# board_smart_switch.net
KiCad netlist of a schematic drawn in EAGLE
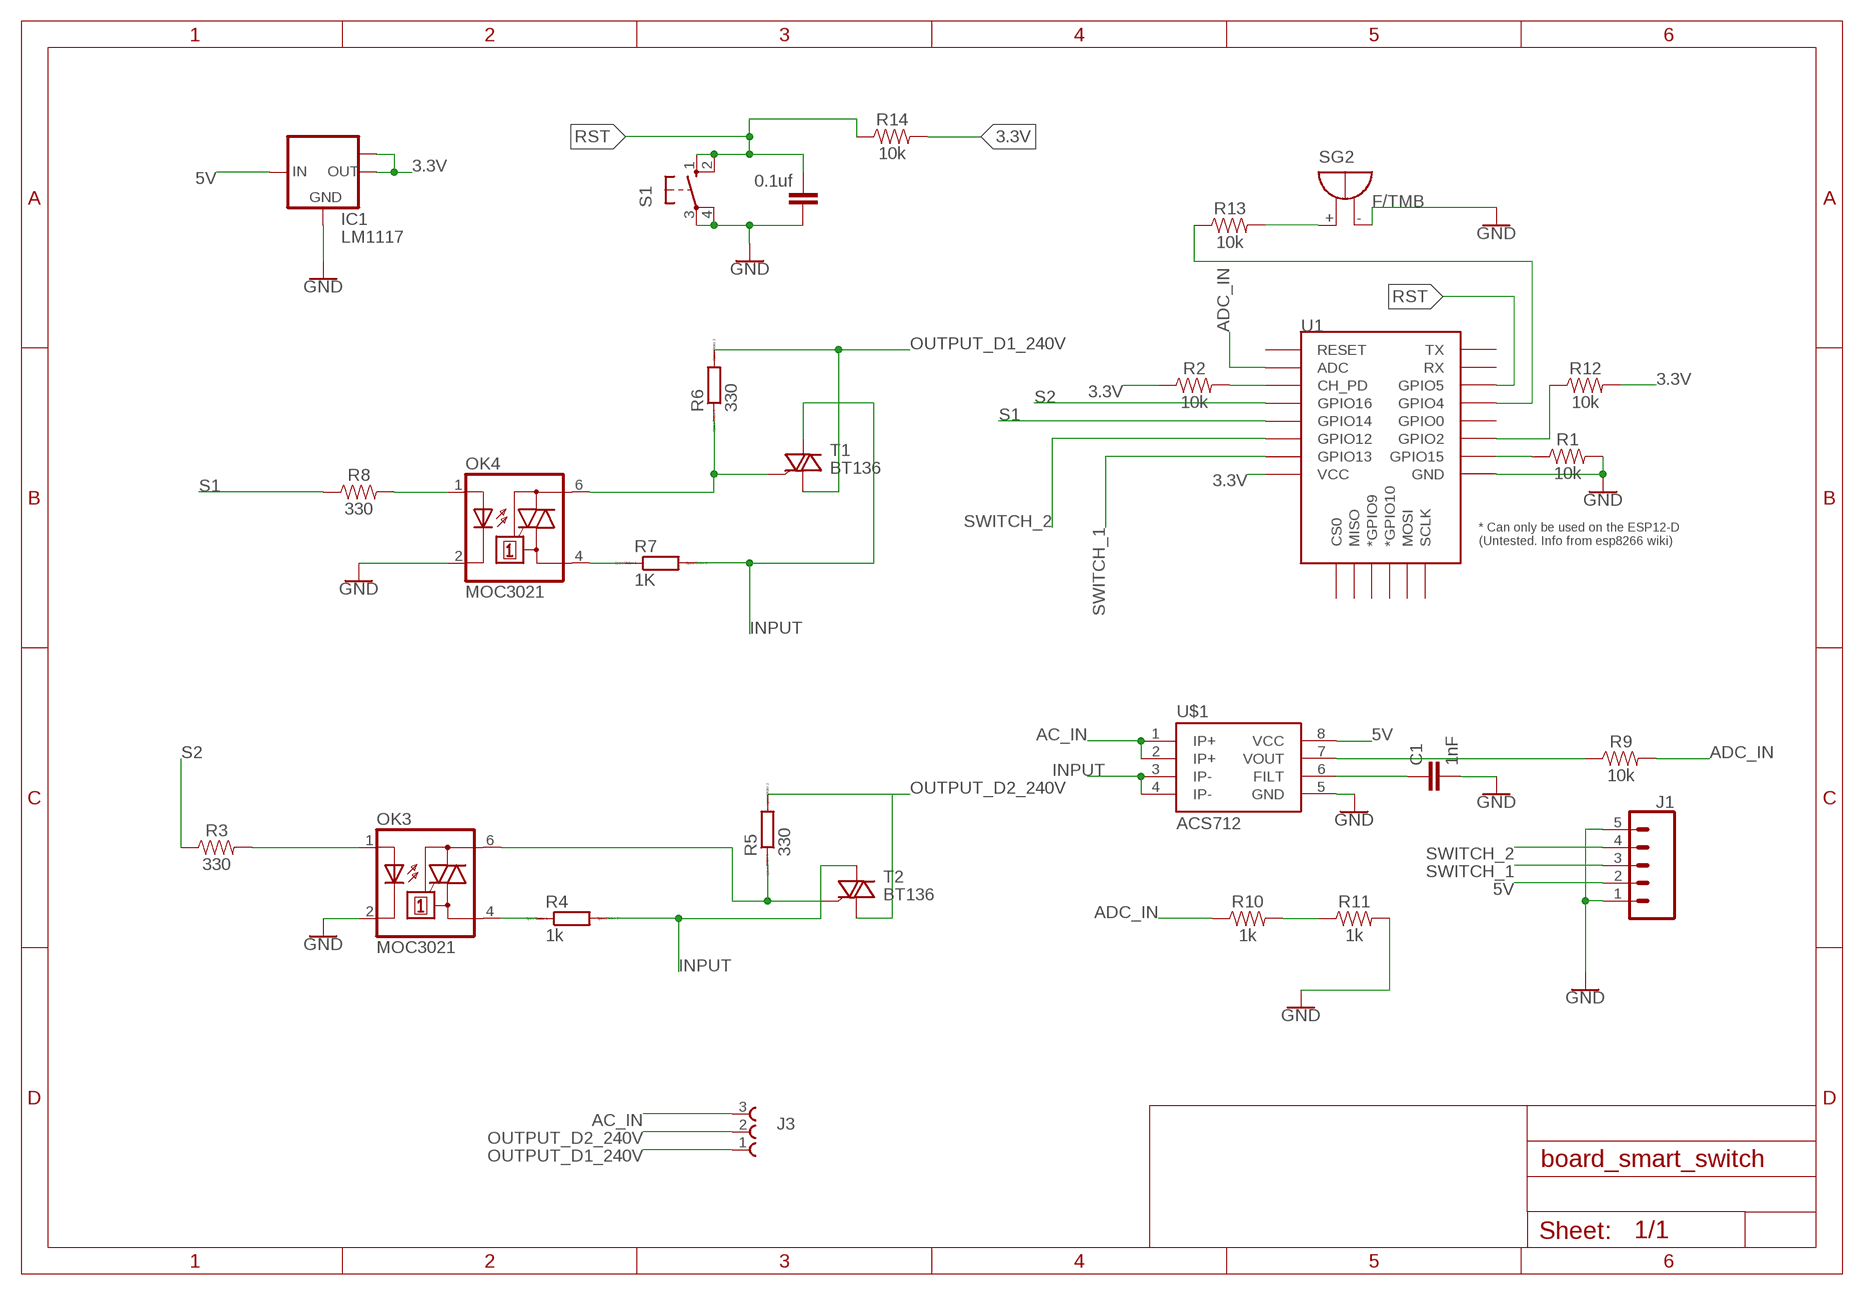
[diagram p0: schematic, sheet 1]

(export (version "E")
  (design (tool "Eeschema 10.0.6"))
  (components
    (comp (ref "C1")
      (value "1nF")
      (footprint "eagle-import:0805")
      (libsource (lib "eagle-import") (part "0.33UF/330NF-0805-50V-10%"))
    )
    (comp (ref "C2")
      (value "0.1uf")
      (footprint "eagle-import:0805")
      (libsource (lib "eagle-import") (part "0.33UF/330NF-0805-50V-10%"))
    )
    (comp (ref "IC1")
      (value "LM1117")
      (footprint "eagle-import:SOT223")
      (libsource (lib "eagle-import") (part "LM1117MPX-3.3"))
    )
    (comp (ref "J1")
      (value "CONN_05JST")
      (footprint "eagle-import:JST-5-PTH")
      (libsource (lib "eagle-import") (part "CONN_05JST"))
    )
    (comp (ref "J3")
      (value "691104700003")
      (footprint "eagle-import:691104700003")
      (libsource (lib "eagle-import") (part "691104700003"))
    )
    (comp (ref "OK3")
      (value "MOC3021")
      (footprint "eagle-import:DIL6-SMD")
      (fields (field (name "MF") "FAIRCHILD SEMICONDUCTOR") (field (name "MPN") "MOC3031SM"))
      (libsource (lib "eagle-import") (part "MOC30S31"))
    )
    (comp (ref "OK4")
      (value "MOC3021")
      (footprint "eagle-import:DIL6-SMD")
      (fields (field (name "MF") "FAIRCHILD SEMICONDUCTOR") (field (name "MPN") "MOC3031SM"))
      (libsource (lib "eagle-import") (part "MOC30S31"))
    )
    (comp (ref "R1")
      (value "10k")
      (footprint "eagle-import:0805")
      (libsource (lib "eagle-import") (part "0.22OHM-0805-1/4W-1%"))
    )
    (comp (ref "R2")
      (value "10k")
      (footprint "eagle-import:0805")
      (libsource (lib "eagle-import") (part "0.22OHM-0805-1/4W-1%"))
    )
    (comp (ref "R3")
      (value "330")
      (footprint "eagle-import:0805")
      (libsource (lib "eagle-import") (part "0.22OHM-0805-1/4W-1%"))
    )
    (comp (ref "R4")
      (value "1k")
      (footprint "eagle-import:R2512")
      (libsource (lib "eagle-import") (part "RR2512"))
    )
    (comp (ref "R5")
      (value "330")
      (footprint "eagle-import:R2512")
      (libsource (lib "eagle-import") (part "RR2512"))
    )
    (comp (ref "R6")
      (value "330")
      (footprint "eagle-import:R2512")
      (libsource (lib "eagle-import") (part "RR2512"))
    )
    (comp (ref "R7")
      (value "1K")
      (footprint "eagle-import:R2512")
      (libsource (lib "eagle-import") (part "RR2512"))
    )
    (comp (ref "R8")
      (value "330")
      (footprint "eagle-import:0805")
      (libsource (lib "eagle-import") (part "0.22OHM-0805-1/4W-1%"))
    )
    (comp (ref "R9")
      (value "10k")
      (footprint "eagle-import:0805")
      (libsource (lib "eagle-import") (part "0.22OHM-0805-1/4W-1%"))
    )
    (comp (ref "R10")
      (value "1k")
      (footprint "eagle-import:0805")
      (libsource (lib "eagle-import") (part "0.22OHM-0805-1/4W-1%"))
    )
    (comp (ref "R11")
      (value "1k")
      (footprint "eagle-import:0805")
      (libsource (lib "eagle-import") (part "0.22OHM-0805-1/4W-1%"))
    )
    (comp (ref "R12")
      (value "10k")
      (footprint "eagle-import:0805")
      (libsource (lib "eagle-import") (part "0.22OHM-0805-1/4W-1%"))
    )
    (comp (ref "R13")
      (value "10k")
      (footprint "eagle-import:0805")
      (libsource (lib "eagle-import") (part "0.22OHM-0805-1/4W-1%"))
    )
    (comp (ref "R14")
      (value "10k")
      (footprint "eagle-import:0805")
      (libsource (lib "eagle-import") (part "0.22OHM-0805-1/4W-1%"))
    )
    (comp (ref "S1")
      (value "10-XX")
      (footprint "eagle-import:B3F-10XX")
      (fields (field (name "MPN") "B3F-1000"))
      (libsource (lib "eagle-import") (part "10-XX"))
    )
    (comp (ref "SG2")
      (value "F/TMB")
      (footprint "eagle-import:F_TMB")
      (libsource (lib "eagle-import") (part "F/TMB"))
    )
    (comp (ref "T1")
      (value "BT136")
      (footprint "eagle-import:TO220AB")
      (libsource (lib "eagle-import") (part "BT136"))
    )
    (comp (ref "T2")
      (value "BT136")
      (footprint "eagle-import:TO220AB")
      (libsource (lib "eagle-import") (part "BT136"))
    )
    (comp (ref "U$1")
      (value "ACS712")
      (footprint "eagle-import:SO08")
      (libsource (lib "eagle-import") (part "ACS712"))
    )
    (comp (ref "U1")
      (value "ESP12ESMD")
      (footprint "eagle-import:ESP12E-SMD")
      (libsource (lib "eagle-import") (part "ESP12ESMD"))
    )
  )
  (nets
    (net (code "1") (name "/5V") (class "Default")
      (node (ref "IC1") (pin "3") (pinfunction "IN_3") (pintype "input"))
      (node (ref "J1") (pin "2") (pinfunction "2_2") (pintype "passive"))
      (node (ref "U$1") (pin "8") (pinfunction "VCC_8") (pintype "bidirectional"))
    )
    (net (code "2") (name "/AC_IN") (class "Default")
      (node (ref "J3") (pin "3") (pinfunction "1_3") (pintype "passive"))
      (node (ref "U$1") (pin "1") (pinfunction "IP+_1") (pintype "bidirectional"))
      (node (ref "U$1") (pin "2") (pinfunction "IP+_2") (pintype "bidirectional"))
    )
    (net (code "3") (name "/ADC_IN") (class "Default")
      (node (ref "R10") (pin "1") (pinfunction "1_1") (pintype "passive"))
      (node (ref "R9") (pin "2") (pinfunction "2_2") (pintype "passive"))
      (node (ref "U1") (pin "ADC") (pinfunction "ADC_ADC") (pintype "bidirectional"))
    )
    (net (code "4") (name "/INPUT") (class "Default")
      (node (ref "R4") (pin "2") (pinfunction "2_2") (pintype "passive"))
      (node (ref "R7") (pin "2") (pinfunction "2_2") (pintype "passive"))
      (node (ref "T1") (pin "2") (pinfunction "A2_2") (pintype "passive"))
      (node (ref "T2") (pin "2") (pinfunction "A2_2") (pintype "passive"))
      (node (ref "U$1") (pin "3") (pinfunction "IP-_3") (pintype "bidirectional"))
      (node (ref "U$1") (pin "4") (pinfunction "IP-_4") (pintype "bidirectional"))
    )
    (net (code "5") (name "/OUTPUT_D1_240V") (class "Default")
      (node (ref "J3") (pin "1") (pinfunction "3_1") (pintype "passive"))
      (node (ref "R6") (pin "2") (pinfunction "2_2") (pintype "passive"))
      (node (ref "T1") (pin "1") (pinfunction "A1_1") (pintype "passive"))
    )
    (net (code "6") (name "/OUTPUT_D2_240V") (class "Default")
      (node (ref "J3") (pin "2") (pinfunction "2_2") (pintype "passive"))
      (node (ref "R5") (pin "2") (pinfunction "2_2") (pintype "passive"))
      (node (ref "T2") (pin "1") (pinfunction "A1_1") (pintype "passive"))
    )
    (net (code "7") (name "/S1") (class "Default")
      (node (ref "R8") (pin "1") (pinfunction "1_1") (pintype "passive"))
      (node (ref "U1") (pin "GPIO14") (pinfunction "GPIO14_GPIO14") (pintype "bidirectional"))
    )
    (net (code "8") (name "/S2") (class "Default")
      (node (ref "R3") (pin "1") (pinfunction "1_1") (pintype "passive"))
      (node (ref "U1") (pin "GPIO16") (pinfunction "GPIO16_GPIO16") (pintype "bidirectional"))
    )
    (net (code "9") (name "/SWITCH_1") (class "Default")
      (node (ref "J1") (pin "3") (pinfunction "3_3") (pintype "passive"))
      (node (ref "U1") (pin "GPIO13") (pinfunction "GPIO13_GPIO13") (pintype "bidirectional"))
    )
    (net (code "10") (name "/SWITCH_2") (class "Default")
      (node (ref "J1") (pin "4") (pinfunction "4_4") (pintype "passive"))
      (node (ref "U1") (pin "GPIO12") (pinfunction "GPIO12_GPIO12") (pintype "bidirectional"))
    )
    (net (code "11") (name "3.3V") (class "Default")
      (node (ref "IC1") (pin "2") (pinfunction "OUT_2") (pintype "passive"))
      (node (ref "IC1") (pin "TAB") (pinfunction "OUT1_TAB") (pintype "passive"))
      (node (ref "R12") (pin "2") (pinfunction "2_2") (pintype "passive"))
      (node (ref "R14") (pin "2") (pinfunction "2_2") (pintype "passive"))
      (node (ref "R2") (pin "1") (pinfunction "1_1") (pintype "passive"))
      (node (ref "U1") (pin "VCC") (pinfunction "VCC_VCC") (pintype "bidirectional"))
    )
    (net (code "12") (name "GND") (class "Default")
      (node (ref "C1") (pin "2") (pinfunction "2_2") (pintype "passive"))
      (node (ref "C2") (pin "1") (pinfunction "1_1") (pintype "passive"))
      (node (ref "IC1") (pin "1") (pinfunction "GND_1") (pintype "input"))
      (node (ref "J1") (pin "1") (pinfunction "1_1") (pintype "passive"))
      (node (ref "J1") (pin "5") (pinfunction "5_5") (pintype "passive"))
      (node (ref "OK3") (pin "2") (pinfunction "C_2") (pintype "passive"))
      (node (ref "OK4") (pin "2") (pinfunction "C_2") (pintype "passive"))
      (node (ref "R1") (pin "2") (pinfunction "2_2") (pintype "passive"))
      (node (ref "R11") (pin "2") (pinfunction "2_2") (pintype "passive"))
      (node (ref "S1") (pin "3") (pinfunction "P_3") (pintype "passive"))
      (node (ref "S1") (pin "4") (pinfunction "P1_4") (pintype "passive"))
      (node (ref "SG2") (pin "-") (pinfunction "-_-") (pintype "passive"))
      (node (ref "U$1") (pin "5") (pinfunction "GND_5") (pintype "bidirectional"))
      (node (ref "U1") (pin "GND") (pinfunction "GND_GND") (pintype "bidirectional"))
    )
    (net (code "13") (name "Net-(OK3-A)") (class "Default")
      (node (ref "OK3") (pin "1") (pinfunction "A_1") (pintype "passive"))
      (node (ref "R3") (pin "2") (pinfunction "2_2") (pintype "passive"))
    )
    (net (code "14") (name "Net-(OK3-A1)") (class "Default")
      (node (ref "OK3") (pin "4") (pinfunction "A1_4") (pintype "passive"))
      (node (ref "R4") (pin "1") (pinfunction "1_1") (pintype "passive"))
    )
    (net (code "15") (name "Net-(OK3-A2)") (class "Default")
      (node (ref "OK3") (pin "6") (pinfunction "A2_6") (pintype "passive"))
      (node (ref "R5") (pin "1") (pinfunction "1_1") (pintype "passive"))
      (node (ref "T2") (pin "3") (pinfunction "G_3") (pintype "passive"))
    )
    (net (code "16") (name "Net-(OK4-A)") (class "Default")
      (node (ref "OK4") (pin "1") (pinfunction "A_1") (pintype "passive"))
      (node (ref "R8") (pin "2") (pinfunction "2_2") (pintype "passive"))
    )
    (net (code "17") (name "Net-(OK4-A1)") (class "Default")
      (node (ref "OK4") (pin "4") (pinfunction "A1_4") (pintype "passive"))
      (node (ref "R7") (pin "1") (pinfunction "1_1") (pintype "passive"))
    )
    (net (code "18") (name "Net-(OK4-A2)") (class "Default")
      (node (ref "OK4") (pin "6") (pinfunction "A2_6") (pintype "passive"))
      (node (ref "R6") (pin "1") (pinfunction "1_1") (pintype "passive"))
      (node (ref "T1") (pin "3") (pinfunction "G_3") (pintype "passive"))
    )
    (net (code "19") (name "Net-(R1-Pad1)") (class "Default")
      (node (ref "R1") (pin "1") (pinfunction "1_1") (pintype "passive"))
      (node (ref "U1") (pin "GPIO15") (pinfunction "GPIO15_GPIO15") (pintype "bidirectional"))
    )
    (net (code "20") (name "Net-(R2-Pad2)") (class "Default")
      (node (ref "R2") (pin "2") (pinfunction "2_2") (pintype "passive"))
      (node (ref "U1") (pin "CH_PD") (pinfunction "CH_PD_CH_PD") (pintype "bidirectional"))
    )
    (net (code "21") (name "Net-(R10-Pad2)") (class "Default")
      (node (ref "R10") (pin "2") (pinfunction "2_2") (pintype "passive"))
      (node (ref "R11") (pin "1") (pinfunction "1_1") (pintype "passive"))
    )
    (net (code "22") (name "Net-(R12-Pad1)") (class "Default")
      (node (ref "R12") (pin "1") (pinfunction "1_1") (pintype "passive"))
      (node (ref "U1") (pin "GPIO2") (pinfunction "GPIO2_GPIO2") (pintype "bidirectional"))
    )
    (net (code "23") (name "Net-(R13-Pad1)") (class "Default")
      (node (ref "R13") (pin "1") (pinfunction "1_1") (pintype "passive"))
      (node (ref "U1") (pin "GPIO4") (pinfunction "GPIO4_GPIO4") (pintype "bidirectional"))
    )
    (net (code "24") (name "Net-(R13-Pad2)") (class "Default")
      (node (ref "R13") (pin "2") (pinfunction "2_2") (pintype "passive"))
      (node (ref "SG2") (pin "+") (pinfunction "+_+") (pintype "passive"))
    )
    (net (code "25") (name "Net-(U$1-FILT)") (class "Default")
      (node (ref "C1") (pin "1") (pinfunction "1_1") (pintype "passive"))
      (node (ref "U$1") (pin "6") (pinfunction "FILT_6") (pintype "bidirectional"))
    )
    (net (code "26") (name "Net-(U$1-VOUT)") (class "Default")
      (node (ref "R9") (pin "1") (pinfunction "1_1") (pintype "passive"))
      (node (ref "U$1") (pin "7") (pinfunction "VOUT_7") (pintype "bidirectional"))
    )
    (net (code "27") (name "RST") (class "Default")
      (node (ref "C2") (pin "2") (pinfunction "2_2") (pintype "passive"))
      (node (ref "R14") (pin "1") (pinfunction "1_1") (pintype "passive"))
      (node (ref "S1") (pin "1") (pinfunction "S_1") (pintype "passive"))
      (node (ref "S1") (pin "2") (pinfunction "S1_2") (pintype "passive"))
      (node (ref "U1") (pin "GPIO5") (pinfunction "GPIO5_GPIO5") (pintype "bidirectional"))
    )
    (net (code "28") (name "unconnected-(U1-*GPIO9-PadGPIO9)") (class "Default")
      (node (ref "U1") (pin "GPIO9") (pinfunction "*GPIO9_GPIO9") (pintype "bidirectional"))
    )
    (net (code "29") (name "unconnected-(U1-*GPIO10-PadGPIO10)") (class "Default")
      (node (ref "U1") (pin "GPIO10") (pinfunction "*GPIO10_GPIO10") (pintype "bidirectional"))
    )
    (net (code "30") (name "unconnected-(U1-PadCS0)") (class "Default")
      (node (ref "U1") (pin "CS0") (pinfunction "CS0_CS0") (pintype "bidirectional"))
    )
    (net (code "31") (name "unconnected-(U1-PadGPIO0)") (class "Default")
      (node (ref "U1") (pin "GPIO0") (pinfunction "GPIO0_GPIO0") (pintype "bidirectional"))
    )
    (net (code "32") (name "unconnected-(U1-PadMISO)") (class "Default")
      (node (ref "U1") (pin "MISO") (pinfunction "MISO_MISO") (pintype "bidirectional"))
    )
    (net (code "33") (name "unconnected-(U1-PadMOSI)") (class "Default")
      (node (ref "U1") (pin "MOSI") (pinfunction "MOSI_MOSI") (pintype "bidirectional"))
    )
    (net (code "34") (name "unconnected-(U1-PadRESET)") (class "Default")
      (node (ref "U1") (pin "RESET") (pinfunction "RESET_RESET") (pintype "bidirectional"))
    )
    (net (code "35") (name "unconnected-(U1-PadSCLK)") (class "Default")
      (node (ref "U1") (pin "SCLK") (pinfunction "SCLK_SCLK") (pintype "bidirectional"))
    )
    (net (code "36") (name "unconnected-(U1-RX-PadRXD0)") (class "Default")
      (node (ref "U1") (pin "RXD0") (pinfunction "RX_RXD0") (pintype "bidirectional"))
    )
    (net (code "37") (name "unconnected-(U1-TX-PadTXD0)") (class "Default")
      (node (ref "U1") (pin "TXD0") (pinfunction "TX_TXD0") (pintype "bidirectional"))
    )
  )
)
